# 4_Power.net
KiCad netlist of a schematic drawn in Altium Designer
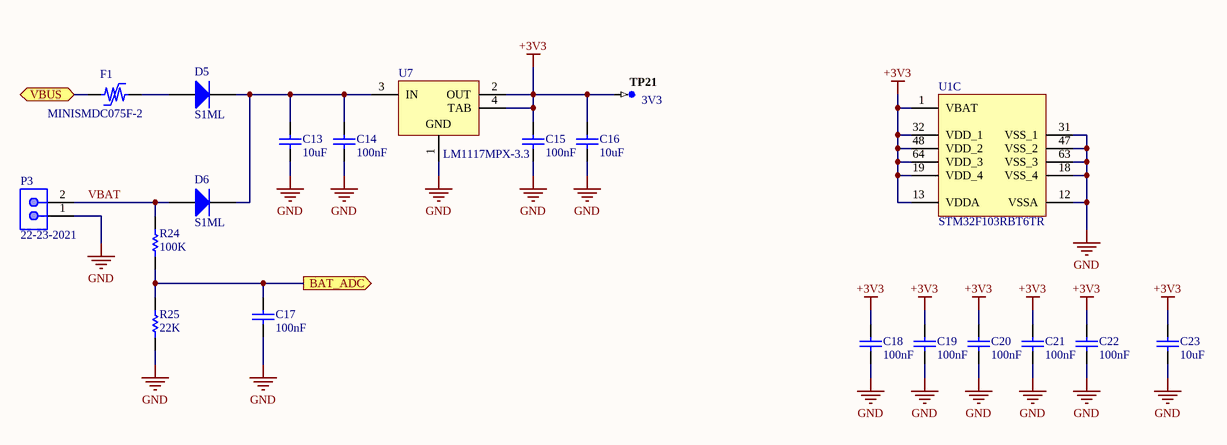
[diagram p0: 4_Power.SchDoc]

(export (version "E")
  (design (tool "Eeschema 10.0.6"))
  (components
    (comp (ref "C13")
      (value "10uF")
      (footprint "CAPC1206(3216)130_L")
      (description "CAP 10uF 16V -20% to +80% 1206 (3216 Metric) Thickness 1.3mm SMD")
      (fields (field (name "TOLERANCE") "-20% to +80%"))
      (libsource (lib "Altium Content Vault") (part "CAP"))
    )
    (comp (ref "C14")
      (value "100nF")
      (footprint "CAPC0603(1608)100_M")
      (description "CAP 100nF 25V ±20% 0603 (1608 Metric) Thickness 1mm SMD")
      (fields (field (name "TOLERANCE") "Â±20%"))
      (libsource (lib "Altium Content Vault") (part "CAP"))
    )
    (comp (ref "C15")
      (value "100nF")
      (footprint "CAPC0603(1608)100_M")
      (description "CAP 100nF 25V ±20% 0603 (1608 Metric) Thickness 1mm SMD")
      (fields (field (name "TOLERANCE") "Â±20%"))
      (libsource (lib "Altium Content Vault") (part "CAP"))
    )
    (comp (ref "C16")
      (value "10uF")
      (footprint "CAPC1206(3216)130_L")
      (description "CAP 10uF 16V -20% to +80% 1206 (3216 Metric) Thickness 1.3mm SMD")
      (fields (field (name "TOLERANCE") "-20% to +80%"))
      (libsource (lib "Altium Content Vault") (part "CAP"))
    )
    (comp (ref "C17")
      (value "100nF")
      (footprint "CAPC0603(1608)100_M")
      (description "CAP 100nF 25V ±20% 0603 (1608 Metric) Thickness 1mm SMD")
      (fields (field (name "TOLERANCE") "Â±20%"))
      (libsource (lib "Altium Content Vault") (part "CAP"))
    )
    (comp (ref "C18")
      (value "100nF")
      (footprint "CAPC0603(1608)100_M")
      (description "CAP 100nF 25V ±20% 0603 (1608 Metric) Thickness 1mm SMD")
      (fields (field (name "TOLERANCE") "Â±20%"))
      (libsource (lib "Altium Content Vault") (part "CAP"))
    )
    (comp (ref "C19")
      (value "100nF")
      (footprint "CAPC0603(1608)100_M")
      (description "CAP 100nF 25V ±20% 0603 (1608 Metric) Thickness 1mm SMD")
      (fields (field (name "TOLERANCE") "Â±20%"))
      (libsource (lib "Altium Content Vault") (part "CAP"))
    )
    (comp (ref "C20")
      (value "100nF")
      (footprint "CAPC0603(1608)100_M")
      (description "CAP 100nF 25V ±20% 0603 (1608 Metric) Thickness 1mm SMD")
      (fields (field (name "TOLERANCE") "Â±20%"))
      (libsource (lib "Altium Content Vault") (part "CAP"))
    )
    (comp (ref "C21")
      (value "100nF")
      (footprint "CAPC0603(1608)100_M")
      (description "CAP 100nF 25V ±20% 0603 (1608 Metric) Thickness 1mm SMD")
      (fields (field (name "TOLERANCE") "Â±20%"))
      (libsource (lib "Altium Content Vault") (part "CAP"))
    )
    (comp (ref "C22")
      (value "100nF")
      (footprint "CAPC0603(1608)100_M")
      (description "CAP 100nF 25V ±20% 0603 (1608 Metric) Thickness 1mm SMD")
      (fields (field (name "TOLERANCE") "Â±20%"))
      (libsource (lib "Altium Content Vault") (part "CAP"))
    )
    (comp (ref "C23")
      (value "10uF")
      (footprint "CAPC1206(3216)130_L")
      (description "CAP 10uF 16V -20% to +80% 1206 (3216 Metric) Thickness 1.3mm SMD")
      (fields (field (name "TOLERANCE") "-20% to +80%"))
      (libsource (lib "Altium Content Vault") (part "CAP"))
    )
    (comp (ref "D5")
      (value "S1ML")
      (footprint "TWS-S1ML_V")
      (description "Rectifier, 1 A, 1.1 V, -55 to 175 degC, 2-Pin SMD, RoHS, Tape and Reel")
      (fields (field (name "MANUFACTURER") "Taiwan Semiconductor"))
      (libsource (lib "Altium Content Vault") (part "D-AK-2"))
    )
    (comp (ref "D6")
      (value "S1ML")
      (footprint "TWS-S1ML_V")
      (description "Rectifier, 1 A, 1.1 V, -55 to 175 degC, 2-Pin SMD, RoHS, Tape and Reel")
      (fields (field (name "MANUFACTURER") "Taiwan Semiconductor"))
      (libsource (lib "Altium Content Vault") (part "D-AK-2"))
    )
    (comp (ref "F1")
      (value "MINISMDC075F-2")
      (footprint "TECO-MINISMDC075F_V")
      (description "PolySwitch Resettable Device, 13.2 V, 0.75 A, -40 to 85 degC, 2-Pin SMD, RoHS, Tape and Reel")
      (fields (field (name "MANUFACTURER") "TE Connectivity"))
      (libsource (lib "Altium Content Vault") (part "PPTC-2"))
    )
    (comp (ref "P3")
      (value "22-23-2021")
      (footprint "MOLX-22-23-2021_V")
      (fields (field (name "MANUFACTURER") "Molex"))
      (libsource (lib "Altium Content Vault") (part "CN-1P-M-R2"))
    )
    (comp (ref "R24")
      (value "100K")
      (footprint "RESC0603(1608)_M")
      (description "100K 0.1W 1% 0603 (1608 Metric)  SMD")
      (fields (field (name "POWER") "0.1 W") (field (name "TOLERANCE") "1 %"))
      (libsource (lib "Altium Content Vault") (part "RES"))
    )
    (comp (ref "R25")
      (value "22K")
      (footprint "RESC0603(1608)_M")
      (description "22K 0.1W 1% 0603 (1608 Metric)  SMD")
      (fields (field (name "POWER") "0.1 W") (field (name "TOLERANCE") "1 %"))
      (libsource (lib "Altium Content Vault") (part "RES"))
    )
    (comp (ref "TP21")
      (value "3V3")
      (footprint "TP-SM-C-100")
      (description "Test Point, Surface Mount, Circular, Pad Diameter 1 mm")
      (fields (field (name "PARTNUMBER") "TP-SM-C-100") (field (name "MANUFACTURER") "No Vendor"))
      (libsource (lib "Altium Content Vault") (part "TP-SM"))
    )
    (comp (ref "U1")
      (value "STM32F103RBT6TR")
      (footprint "STM-LQFP64_N")
      (libsource (lib "Altium Content Vault") (part "MC-ARM-STM32F103X8_B-SQ64"))
    )
    (comp (ref "U7")
      (value "LM1117MPX-3.3")
      (footprint "MP04A_N")
      (description "800mA Low-Dropout Linear Regulator, 4-pin SOT-223")
      (fields (field (name "MANUFACTURER") "National Semiconductor"))
      (libsource (lib "Altium Content Vault") (part "PM-REG-LM1086-SOT4"))
    )
  )
  (nets
    (net (code "1") (name "+3V3") (class "Default")
      (node (ref "C15") (pin "2") (pinfunction "2_2") (pintype "passive"))
      (node (ref "C16") (pin "2") (pinfunction "2_2") (pintype "passive"))
      (node (ref "C18") (pin "2") (pinfunction "2_2") (pintype "passive"))
      (node (ref "C19") (pin "2") (pinfunction "2_2") (pintype "passive"))
      (node (ref "C20") (pin "2") (pinfunction "2_2") (pintype "passive"))
      (node (ref "C21") (pin "2") (pinfunction "2_2") (pintype "passive"))
      (node (ref "C22") (pin "2") (pinfunction "2_2") (pintype "passive"))
      (node (ref "C23") (pin "2") (pinfunction "2_2") (pintype "passive"))
      (node (ref "TP21") (pin "1") (pinfunction "1_1") (pintype "input"))
      (node (ref "U1") (pin "1") (pinfunction "VBAT_1") (pintype "power_in"))
      (node (ref "U1") (pin "13") (pinfunction "VDDA_13") (pintype "power_in"))
      (node (ref "U1") (pin "19") (pinfunction "VDD_4_19") (pintype "power_in"))
      (node (ref "U1") (pin "32") (pinfunction "VDD_1_32") (pintype "power_in"))
      (node (ref "U1") (pin "48") (pinfunction "VDD_2_48") (pintype "power_in"))
      (node (ref "U1") (pin "64") (pinfunction "VDD_3_64") (pintype "power_in"))
      (node (ref "U7") (pin "2") (pinfunction "OUT_2") (pintype "power_in"))
      (node (ref "U7") (pin "4") (pinfunction "TAB_4") (pintype "power_in"))
    )
    (net (code "2") (name "/BAT_ADC") (class "Default")
      (node (ref "C17") (pin "2") (pinfunction "2_2") (pintype "passive"))
      (node (ref "R24") (pin "1") (pinfunction "1_1") (pintype "passive"))
      (node (ref "R25") (pin "2") (pinfunction "2_2") (pintype "passive"))
    )
    (net (code "3") (name "/VBAT") (class "Default")
      (node (ref "D6") (pin "1") (pinfunction "A_1") (pintype "passive"))
      (node (ref "P3") (pin "2") (pinfunction "2_2") (pintype "passive"))
      (node (ref "R24") (pin "2") (pinfunction "2_2") (pintype "passive"))
    )
    (net (code "4") (name "/VBUS") (class "Default")
      (node (ref "F1") (pin "1") (pinfunction "1_1") (pintype "passive"))
    )
    (net (code "5") (name "GND") (class "Default")
      (node (ref "C13") (pin "1") (pinfunction "1_1") (pintype "passive"))
      (node (ref "C14") (pin "1") (pinfunction "1_1") (pintype "passive"))
      (node (ref "C15") (pin "1") (pinfunction "1_1") (pintype "passive"))
      (node (ref "C16") (pin "1") (pinfunction "1_1") (pintype "passive"))
      (node (ref "C17") (pin "1") (pinfunction "1_1") (pintype "passive"))
      (node (ref "C18") (pin "1") (pinfunction "1_1") (pintype "passive"))
      (node (ref "C19") (pin "1") (pinfunction "1_1") (pintype "passive"))
      (node (ref "C20") (pin "1") (pinfunction "1_1") (pintype "passive"))
      (node (ref "C21") (pin "1") (pinfunction "1_1") (pintype "passive"))
      (node (ref "C22") (pin "1") (pinfunction "1_1") (pintype "passive"))
      (node (ref "C23") (pin "1") (pinfunction "1_1") (pintype "passive"))
      (node (ref "P3") (pin "1") (pinfunction "1_1") (pintype "passive"))
      (node (ref "R25") (pin "1") (pinfunction "1_1") (pintype "passive"))
      (node (ref "U1") (pin "12") (pinfunction "VSSA_12") (pintype "power_in"))
      (node (ref "U1") (pin "18") (pinfunction "VSS_4_18") (pintype "power_in"))
      (node (ref "U1") (pin "31") (pinfunction "VSS_1_31") (pintype "power_in"))
      (node (ref "U1") (pin "47") (pinfunction "VSS_2_47") (pintype "power_in"))
      (node (ref "U1") (pin "63") (pinfunction "VSS_3_63") (pintype "power_in"))
      (node (ref "U7") (pin "1") (pinfunction "GND_1") (pintype "power_in"))
    )
    (net (code "6") (name "Net-(D5-A)") (class "Default")
      (node (ref "D5") (pin "1") (pinfunction "A_1") (pintype "passive"))
      (node (ref "F1") (pin "2") (pinfunction "2_2") (pintype "passive"))
    )
    (net (code "7") (name "Net-(D5-K)") (class "Default")
      (node (ref "C13") (pin "2") (pinfunction "2_2") (pintype "passive"))
      (node (ref "C14") (pin "2") (pinfunction "2_2") (pintype "passive"))
      (node (ref "D5") (pin "2") (pinfunction "K_2") (pintype "passive"))
      (node (ref "D6") (pin "2") (pinfunction "K_2") (pintype "passive"))
      (node (ref "U7") (pin "3") (pinfunction "IN_3") (pintype "power_in"))
    )
  )
)
